# 06_RFID.net
KiCad netlist of a schematic drawn in Altium Designer
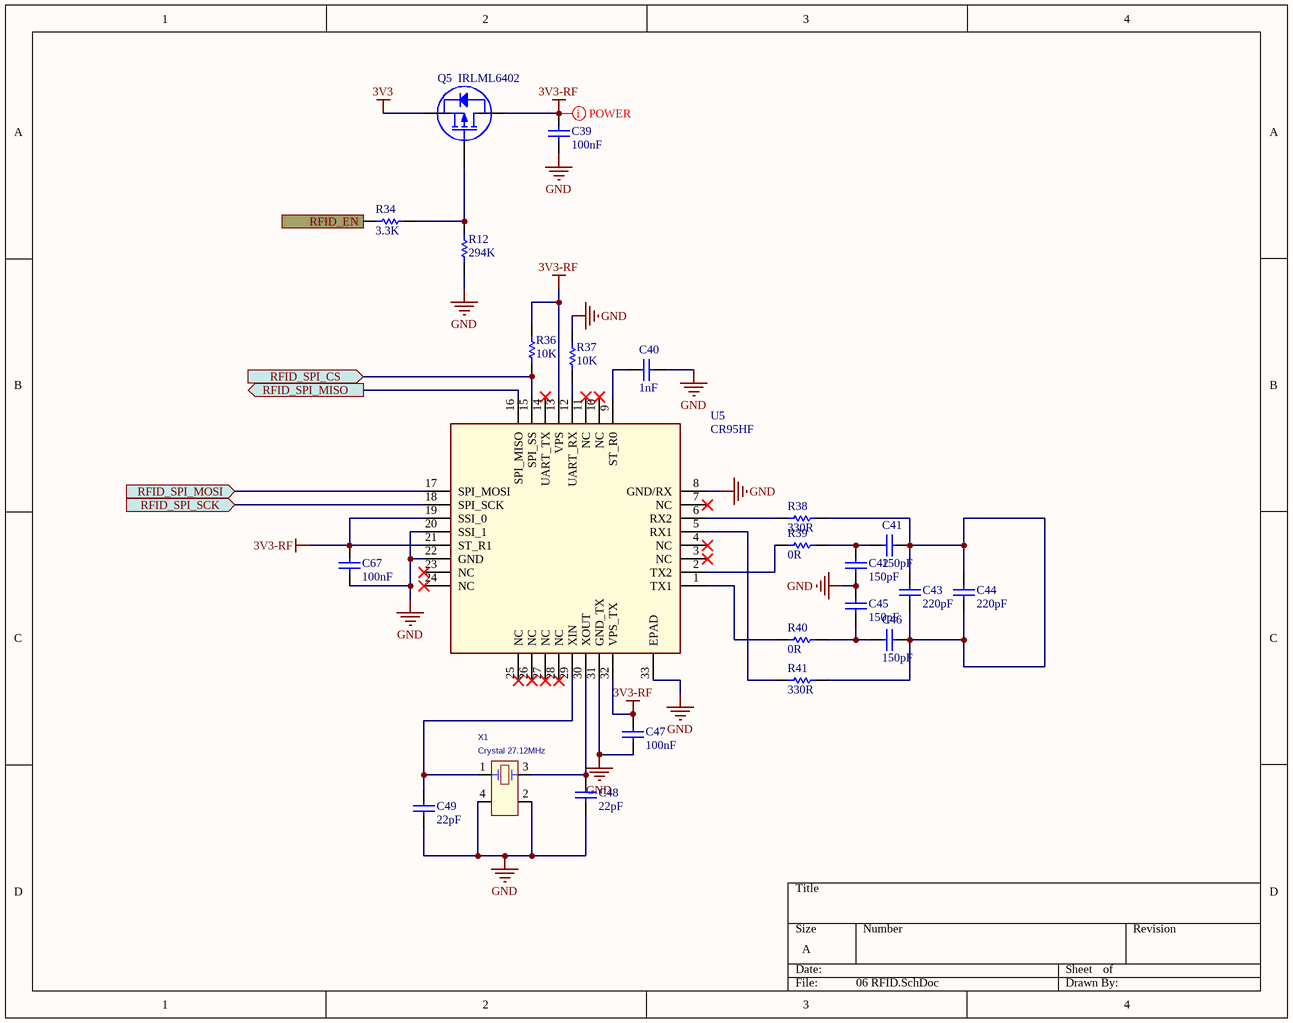
[diagram p0: 06 RFID.SchDoc]

(export (version "E")
  (design (tool "Eeschema 10.0.6"))
  (components
    (comp (ref "C39")
      (value "100nF")
      (footprint "0603 - C")
      (description "CAP CER 100nF 50V C0G/NP0 0603 ±5%")
      (fields (field (name "VOLTAGE") "50V") (field (name "MPN") "CL10C104JB8NNNC"))
      (libsource (lib "Library_Chip") (part "Cap 0603 100nF"))
    )
    (comp (ref "C40")
      (value "1nF")
      (footprint "0603 - C")
      (description "CAP CER 1000PF 50V C0G/NP0 0603")
      (fields (field (name "MPN") "CL10C102JB8NNNC") (field (name "MFR") "SAMSUNG"))
      (libsource (lib "Library_Chip") (part "Cap 0603 1nF"))
    )
    (comp (ref "C41")
      (value "150pF")
      (footprint "0603 - C")
      (description "CAP CER 150PF 50V C0G/NP0 0603")
      (fields (field (name "MPN") "CL10C151JB8NNNC") (field (name "MFR") "SAMSUNG"))
      (libsource (lib "Library_Chip") (part "Cap 0603 150pF"))
    )
    (comp (ref "C42")
      (value "150pF")
      (footprint "0603 - C")
      (description "CAP CER 150PF 50V C0G/NP0 0603")
      (fields (field (name "MPN") "CL10C151JB8NNNC") (field (name "MFR") "SAMSUNG"))
      (libsource (lib "Library_Chip") (part "Cap 0603 150pF"))
    )
    (comp (ref "C43")
      (value "220pF")
      (footprint "0603 - C")
      (description "CAP CER 220PF 50V C0G/NP0 0603")
      (fields (field (name "MPN") "CL10C221JB8NNNC") (field (name "MFR") "SAMSUNG"))
      (libsource (lib "Library_Chip") (part "Cap 0603 220pF"))
    )
    (comp (ref "C44")
      (value "220pF")
      (footprint "0603 - C")
      (description "CAP CER 220PF 50V C0G/NP0 0603")
      (fields (field (name "MPN") "CL10C221JB8NNNC") (field (name "MFR") "SAMSUNG"))
      (libsource (lib "Library_Chip") (part "Cap 0603 220pF"))
    )
    (comp (ref "C45")
      (value "150pF")
      (footprint "0603 - C")
      (description "CAP CER 150PF 50V C0G/NP0 0603")
      (fields (field (name "MPN") "CL10C151JB8NNNC") (field (name "MFR") "SAMSUNG"))
      (libsource (lib "Library_Chip") (part "Cap 0603 150pF"))
    )
    (comp (ref "C46")
      (value "150pF")
      (footprint "0603 - C")
      (description "CAP CER 150PF 50V C0G/NP0 0603")
      (fields (field (name "MPN") "CL10C151JB8NNNC") (field (name "MFR") "SAMSUNG"))
      (libsource (lib "Library_Chip") (part "Cap 0603 150pF"))
    )
    (comp (ref "C47")
      (value "100nF")
      (footprint "0603 - C")
      (description "CAP CER 100nF 50V C0G/NP0 0603 ±5%")
      (fields (field (name "MPN") "CL10C104JB8NNNC") (field (name "MFR") "SAMSUNG"))
      (libsource (lib "Library_Chip") (part "Cap 0603 100nF"))
    )
    (comp (ref "C48")
      (value "22pF")
      (footprint "0603 - C")
      (description "CAP CER 22PF 50V C0G/NP0 0603")
      (fields (field (name "MPN") "CL10C220JB8NNNC") (field (name "MFR") "SAMSUNG"))
      (libsource (lib "Library_Chip") (part "Cap 0603 22pF"))
    )
    (comp (ref "C49")
      (value "22pF")
      (footprint "0603 - C")
      (description "CAP CER 22PF 50V C0G/NP0 0603")
      (fields (field (name "MPN") "CL10C220JB8NNNC") (field (name "MFR") "SAMSUNG"))
      (libsource (lib "Library_Chip") (part "Cap 0603 22pF"))
    )
    (comp (ref "C67")
      (value "100nF")
      (footprint "0603 - C")
      (description "CAP CER 100nF 50V C0G/NP0 0603 ±5%")
      (fields (field (name "VOLTAGE") "50V") (field (name "MPN") "CL10C104JB8NNNC"))
      (libsource (lib "Library_Chip") (part "Cap 0603 100nF"))
    )
    (comp (ref "Q5")
      (value "IRLML6402")
      (footprint "SOT23B")
      (description "MOSFET P-CH 30V 3.6A SOT-23-3")
      (fields (field (name "MPN") "IRLML6402TRPBF") (field (name "MFR") "Infineon Technologies"))
      (libsource (lib "Library_Chip") (part "MOSFET IRLML6402TRPBF"))
    )
    (comp (ref "R12")
      (value "294K")
      (footprint "0603 - R")
      (description "RES SMD 294K OHM 1% 1/10W 0603")
      (fields (field (name "MFR") "Yageo") (field (name "MPN") "RC0603FR-07294KL"))
      (libsource (lib "Library_Chip") (part "Res 0603 294K"))
    )
    (comp (ref "R34")
      (value "3.3K")
      (footprint "0603 - R")
      (description "RES SMD 3.3K OHM 1% 1/10W 0603")
      (fields (field (name "MFR") "Yageo") (field (name "MPN") "RC0603FR-073K3L"))
      (libsource (lib "Library_Chip") (part "Res 0603 3.3K"))
    )
    (comp (ref "R36")
      (value "10K")
      (footprint "0603 - R")
      (description "RES SMD 10K OHM 1% 1/10W 0603")
      (fields (field (name "MFR") "Yageo") (field (name "MPN") "RC0603FR-0710KL"))
      (libsource (lib "Library_Chip") (part "Res 0603 10K"))
    )
    (comp (ref "R37")
      (value "10K")
      (footprint "0603 - R")
      (description "RES SMD 10K OHM 1% 1/10W 0603")
      (fields (field (name "MFR") "Yageo") (field (name "MPN") "RC0603FR-0710KL"))
      (libsource (lib "Library_Chip") (part "Res 0603 10K"))
    )
    (comp (ref "R38")
      (value "330R")
      (footprint "0603 - R")
      (description "RES SMD 330OHM 1% 1/10W 0603")
      (fields (field (name "MFR") "Yageo") (field (name "MPN") "RC0603FR-07330RL"))
      (libsource (lib "Library_Chip") (part "Res 0603 330R"))
    )
    (comp (ref "R39")
      (value "0R")
      (footprint "0603 - R")
      (description "RES SMD 0 OHM JUMPER 1/10W 0603")
      (fields (field (name "MFR") "Yageo") (field (name "MPN") "RC0603FR-070RL"))
      (libsource (lib "Library_Chip") (part "Res 0603 0R"))
    )
    (comp (ref "R40")
      (value "0R")
      (footprint "0603 - R")
      (description "RES SMD 0 OHM JUMPER 1/10W 0603")
      (fields (field (name "MFR") "Yageo") (field (name "MPN") "RC0603FR-070RL"))
      (libsource (lib "Library_Chip") (part "Res 0603 0R"))
    )
    (comp (ref "R41")
      (value "330R")
      (footprint "0603 - R")
      (description "RES SMD 330OHM 1% 1/10W 0603")
      (fields (field (name "MFR") "Yageo") (field (name "MPN") "RC0603FR-07330RL"))
      (libsource (lib "Library_Chip") (part "Res 0603 330R"))
    )
    (comp (ref "U5")
      (value "CR95HF")
      (footprint "32-VFQFN")
      (description "IC RFID RDR/TRN 13.56MZ 32VFQFPN")
      (fields (field (name "MPN") "CR95HF-VMD5T") (field (name "MFR") "ST"))
      (libsource (lib "Library_IC") (part "CR95HF"))
    )
    (comp (ref "X1")
      (value "Crystal 27.12MHz")
      (footprint "Crystal 2016")
      (description "CRYSTAL 27.12MHz RoHS")
      (fields (field (name "MPN") "XRCGB27M120F3M00R0") (field (name "MFR") "Murata"))
      (libsource (lib "Library_Chip") (part "XTAL-XRCBG27M"))
    )
  )
  (nets
    (net (code "1") (name "/RFID_EN") (class "Default")
      (node (ref "R34") (pin "1") (pinfunction "1_1") (pintype "passive"))
    )
    (net (code "2") (name "/RFID_SPI_CS") (class "Default")
      (node (ref "R36") (pin "1") (pinfunction "1_1") (pintype "passive"))
      (node (ref "U5") (pin "15") (pinfunction "SPI_SS_15") (pintype "passive"))
    )
    (net (code "3") (name "/RFID_SPI_MISO") (class "Default")
      (node (ref "U5") (pin "16") (pinfunction "SPI_MISO_16") (pintype "passive"))
    )
    (net (code "4") (name "/RFID_SPI_MOSI") (class "Default")
      (node (ref "U5") (pin "17") (pinfunction "SPI_MOSI_17") (pintype "passive"))
    )
    (net (code "5") (name "/RFID_SPI_SCK") (class "Default")
      (node (ref "U5") (pin "18") (pinfunction "SPI_SCK_18") (pintype "passive"))
    )
    (net (code "6") (name "3V3") (class "Default")
      (node (ref "Q5") (pin "2") (pinfunction "S_2") (pintype "passive"))
    )
    (net (code "7") (name "3V3-RF") (class "Default")
      (node (ref "C39") (pin "2") (pinfunction "2_2") (pintype "passive"))
      (node (ref "C47") (pin "2") (pinfunction "2_2") (pintype "passive"))
      (node (ref "C67") (pin "2") (pinfunction "2_2") (pintype "passive"))
      (node (ref "Q5") (pin "3") (pinfunction "D_3") (pintype "passive"))
      (node (ref "R36") (pin "2") (pinfunction "2_2") (pintype "passive"))
      (node (ref "U5") (pin "13") (pinfunction "VPS_13") (pintype "passive"))
      (node (ref "U5") (pin "19") (pinfunction "SSI_0_19") (pintype "passive"))
      (node (ref "U5") (pin "21") (pinfunction "ST_R1_21") (pintype "passive"))
      (node (ref "U5") (pin "32") (pinfunction "VPS_TX_32") (pintype "passive"))
    )
    (net (code "8") (name "GND") (class "Default")
      (node (ref "C39") (pin "1") (pinfunction "1_1") (pintype "passive"))
      (node (ref "C40") (pin "2") (pinfunction "2_2") (pintype "passive"))
      (node (ref "C42") (pin "1") (pinfunction "1_1") (pintype "passive"))
      (node (ref "C45") (pin "2") (pinfunction "2_2") (pintype "passive"))
      (node (ref "C47") (pin "1") (pinfunction "1_1") (pintype "passive"))
      (node (ref "C48") (pin "1") (pinfunction "1_1") (pintype "passive"))
      (node (ref "C49") (pin "1") (pinfunction "1_1") (pintype "passive"))
      (node (ref "C67") (pin "1") (pinfunction "1_1") (pintype "passive"))
      (node (ref "R12") (pin "1") (pinfunction "1_1") (pintype "passive"))
      (node (ref "R37") (pin "2") (pinfunction "2_2") (pintype "passive"))
      (node (ref "U5") (pin "20") (pinfunction "SSI_1_20") (pintype "passive"))
      (node (ref "U5") (pin "22") (pinfunction "GND_22") (pintype "passive"))
      (node (ref "U5") (pin "31") (pinfunction "GND_TX_31") (pintype "passive"))
      (node (ref "U5") (pin "33") (pinfunction "EPAD_33") (pintype "passive"))
      (node (ref "U5") (pin "8") (pinfunction "GND/RX_8") (pintype "passive"))
      (node (ref "X1") (pin "2") (pinfunction "GND_2") (pintype "power_in"))
      (node (ref "X1") (pin "4") (pinfunction "GND_4") (pintype "power_in"))
    )
    (net (code "9") (name "Net-(C41-Pad1)") (class "Default")
      (node (ref "C41") (pin "1") (pinfunction "1_1") (pintype "passive"))
      (node (ref "C42") (pin "2") (pinfunction "2_2") (pintype "passive"))
      (node (ref "R39") (pin "2") (pinfunction "2_2") (pintype "passive"))
    )
    (net (code "10") (name "Net-(C41-Pad2)") (class "Default")
      (node (ref "C41") (pin "2") (pinfunction "2_2") (pintype "passive"))
      (node (ref "C43") (pin "1") (pinfunction "1_1") (pintype "passive"))
      (node (ref "C43") (pin "2") (pinfunction "2_2") (pintype "passive"))
      (node (ref "C44") (pin "1") (pinfunction "1_1") (pintype "passive"))
      (node (ref "C44") (pin "2") (pinfunction "2_2") (pintype "passive"))
      (node (ref "C46") (pin "2") (pinfunction "2_2") (pintype "passive"))
      (node (ref "R38") (pin "2") (pinfunction "2_2") (pintype "passive"))
      (node (ref "R41") (pin "2") (pinfunction "2_2") (pintype "passive"))
    )
    (net (code "11") (name "Net-(C45-Pad1)") (class "Default")
      (node (ref "C45") (pin "1") (pinfunction "1_1") (pintype "passive"))
      (node (ref "C46") (pin "1") (pinfunction "1_1") (pintype "passive"))
      (node (ref "R40") (pin "2") (pinfunction "2_2") (pintype "passive"))
    )
    (net (code "12") (name "Net-(Q5-G)") (class "Default")
      (node (ref "Q5") (pin "1") (pinfunction "G_1") (pintype "passive"))
      (node (ref "R12") (pin "2") (pinfunction "2_2") (pintype "passive"))
      (node (ref "R34") (pin "2") (pinfunction "2_2") (pintype "passive"))
    )
    (net (code "13") (name "Net-(U5-RX1)") (class "Default")
      (node (ref "R41") (pin "1") (pinfunction "1_1") (pintype "passive"))
      (node (ref "U5") (pin "5") (pinfunction "RX1_5") (pintype "passive"))
    )
    (net (code "14") (name "Net-(U5-RX2)") (class "Default")
      (node (ref "R38") (pin "1") (pinfunction "1_1") (pintype "passive"))
      (node (ref "U5") (pin "6") (pinfunction "RX2_6") (pintype "passive"))
    )
    (net (code "15") (name "Net-(U5-ST_R0)") (class "Default")
      (node (ref "C40") (pin "1") (pinfunction "1_1") (pintype "passive"))
      (node (ref "U5") (pin "9") (pinfunction "ST_R0_9") (pintype "passive"))
    )
    (net (code "16") (name "Net-(U5-TX1)") (class "Default")
      (node (ref "R40") (pin "1") (pinfunction "1_1") (pintype "passive"))
      (node (ref "U5") (pin "1") (pinfunction "TX1_1") (pintype "passive"))
    )
    (net (code "17") (name "Net-(U5-TX2)") (class "Default")
      (node (ref "R39") (pin "1") (pinfunction "1_1") (pintype "passive"))
      (node (ref "U5") (pin "2") (pinfunction "TX2_2") (pintype "passive"))
    )
    (net (code "18") (name "Net-(U5-UART_RX)") (class "Default")
      (node (ref "R37") (pin "1") (pinfunction "1_1") (pintype "passive"))
      (node (ref "U5") (pin "12") (pinfunction "UART_RX_12") (pintype "passive"))
    )
    (net (code "19") (name "Net-(U5-XIN)") (class "Default")
      (node (ref "C49") (pin "2") (pinfunction "2_2") (pintype "passive"))
      (node (ref "U5") (pin "29") (pinfunction "XIN_29") (pintype "passive"))
      (node (ref "X1") (pin "1") (pinfunction "OSC1_1") (pintype "passive"))
    )
    (net (code "20") (name "Net-(U5-XOUT)") (class "Default")
      (node (ref "C48") (pin "2") (pinfunction "2_2") (pintype "passive"))
      (node (ref "U5") (pin "30") (pinfunction "XOUT_30") (pintype "passive"))
      (node (ref "X1") (pin "3") (pinfunction "OSC2_3") (pintype "passive"))
    )
    (net (code "21") (name "unconnected-(U5-NC-Pad3)") (class "Default")
      (node (ref "U5") (pin "3") (pinfunction "NC_3") (pintype "passive+no_connect"))
    )
    (net (code "22") (name "unconnected-(U5-NC-Pad4)") (class "Default")
      (node (ref "U5") (pin "4") (pinfunction "NC_4") (pintype "passive+no_connect"))
    )
    (net (code "23") (name "unconnected-(U5-NC-Pad7)") (class "Default")
      (node (ref "U5") (pin "7") (pinfunction "NC_7") (pintype "passive+no_connect"))
    )
    (net (code "24") (name "unconnected-(U5-NC-Pad10)") (class "Default")
      (node (ref "U5") (pin "10") (pinfunction "NC_10") (pintype "passive+no_connect"))
    )
    (net (code "25") (name "unconnected-(U5-NC-Pad11)") (class "Default")
      (node (ref "U5") (pin "11") (pinfunction "NC_11") (pintype "passive+no_connect"))
    )
    (net (code "26") (name "unconnected-(U5-NC-Pad23)") (class "Default")
      (node (ref "U5") (pin "23") (pinfunction "NC_23") (pintype "passive+no_connect"))
    )
    (net (code "27") (name "unconnected-(U5-NC-Pad24)") (class "Default")
      (node (ref "U5") (pin "24") (pinfunction "NC_24") (pintype "passive+no_connect"))
    )
    (net (code "28") (name "unconnected-(U5-NC-Pad25)") (class "Default")
      (node (ref "U5") (pin "25") (pinfunction "NC_25") (pintype "passive+no_connect"))
    )
    (net (code "29") (name "unconnected-(U5-NC-Pad26)") (class "Default")
      (node (ref "U5") (pin "26") (pinfunction "NC_26") (pintype "passive+no_connect"))
    )
    (net (code "30") (name "unconnected-(U5-NC-Pad27)") (class "Default")
      (node (ref "U5") (pin "27") (pinfunction "NC_27") (pintype "passive+no_connect"))
    )
    (net (code "31") (name "unconnected-(U5-NC-Pad28)") (class "Default")
      (node (ref "U5") (pin "28") (pinfunction "NC_28") (pintype "passive+no_connect"))
    )
    (net (code "32") (name "unconnected-(U5-UART_TX-Pad14)") (class "Default")
      (node (ref "U5") (pin "14") (pinfunction "UART_TX_14") (pintype "passive+no_connect"))
    )
  )
)
